# 08_INPUTCAPTURE_ENCODER.net
KiCad netlist of a schematic drawn in Altium Designer
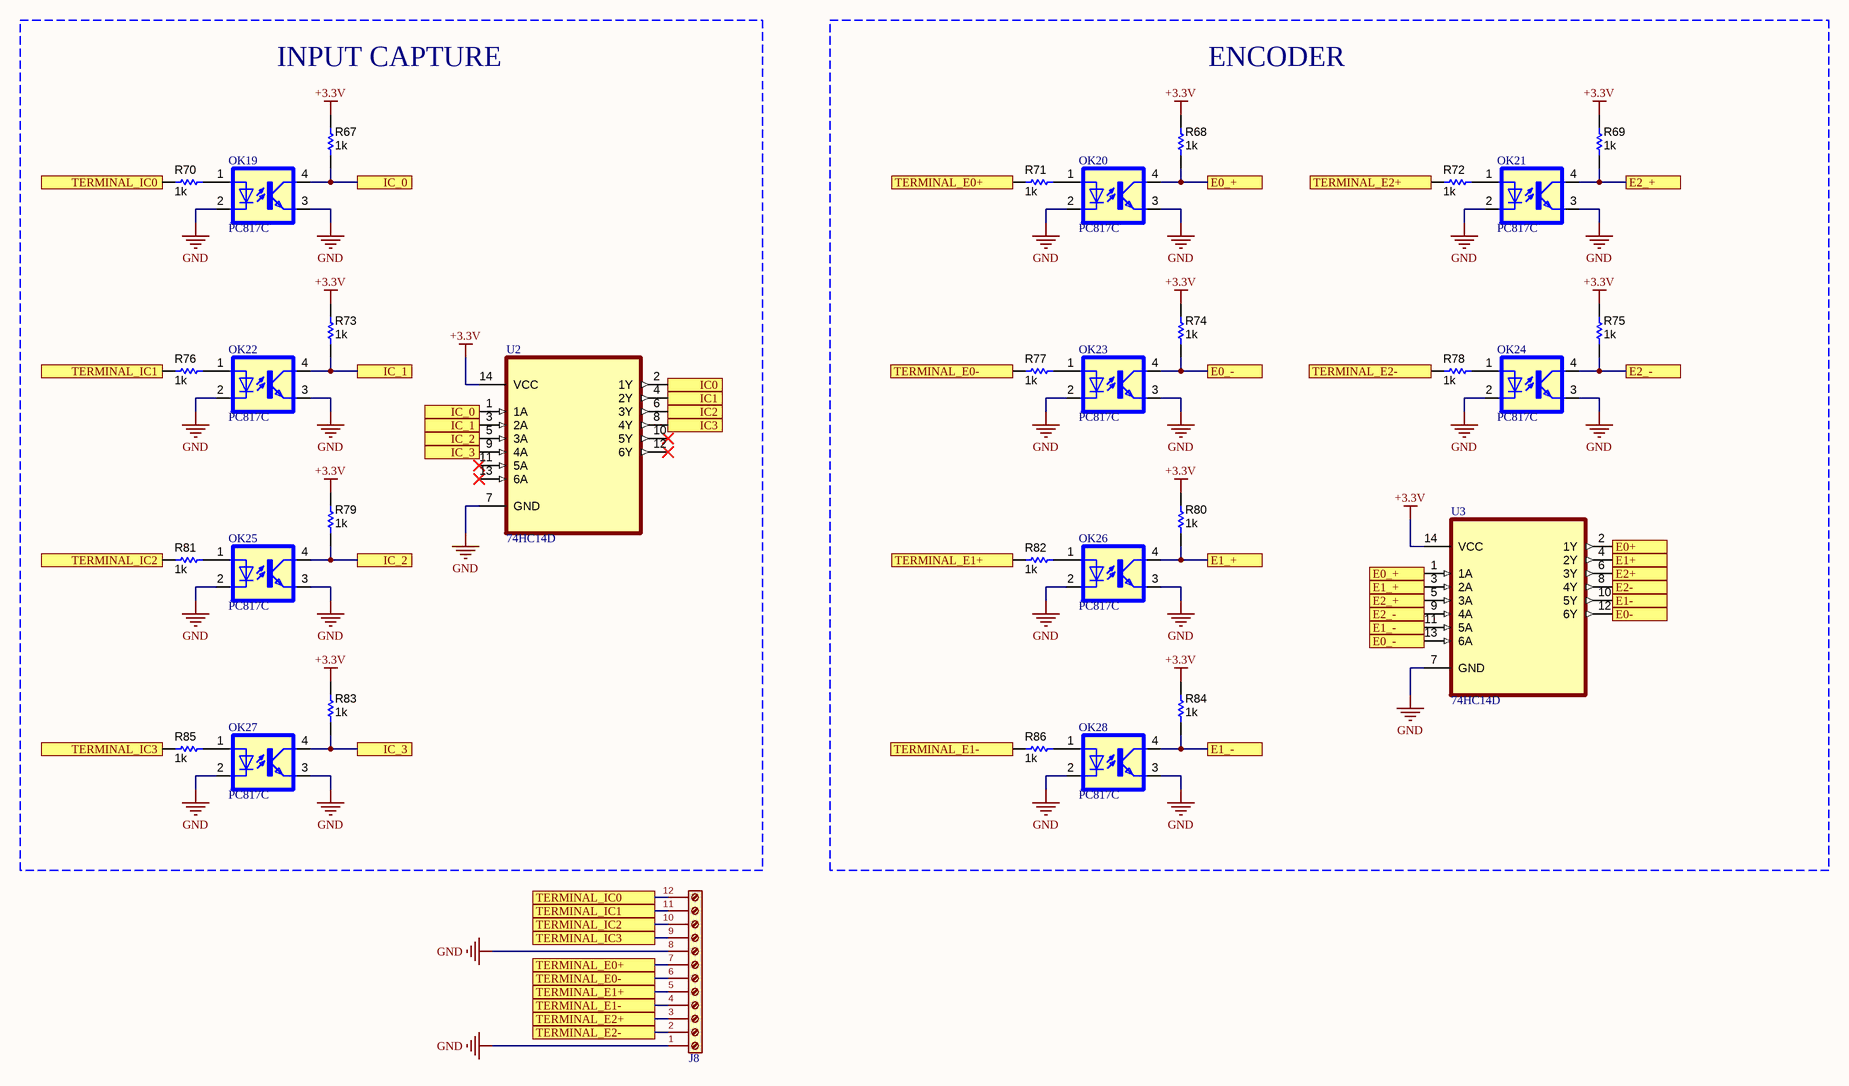
[diagram p0: 08_INPUTCAPTURE_ENCODER.SchDoc]

(export (version "E")
  (design (tool "Eeschema 10.0.6"))
  (components
    (comp (ref "J8")
      (value "Terminal_01x12_P5.00")
      (footprint "TerminalBlock_Phoenix_PT-1,5-12-5.0-H_1x12_P5.00mm_Horizontal")
      (libsource (lib "PROC051C_AWR1843BOOST_RevC") (part "Terminal_01x12_P5.00"))
    )
    (comp (ref "OK19")
      (value "PC817C")
      (footprint "SOP254P975X460-4N")
      (description "RF Mixer IC Cellular, DCS, PCS, W-CDMA, WLAN Up Converter 50MHz ~ 400MHz 6-SuperMiniMold")
      (fields (field (name "MF") "Renesas Electronics America Inc") (field (name "MP") "PC817"))
      (libsource (lib "PROC051C_AWR1843BOOST_RevC") (part "PC817C"))
    )
    (comp (ref "OK20")
      (value "PC817C")
      (footprint "SOP254P975X460-4N")
      (description "RF Mixer IC Cellular, DCS, PCS, W-CDMA, WLAN Up Converter 50MHz ~ 400MHz 6-SuperMiniMold")
      (fields (field (name "MF") "Renesas Electronics America Inc") (field (name "MP") "PC817"))
      (libsource (lib "PROC051C_AWR1843BOOST_RevC") (part "PC817C"))
    )
    (comp (ref "OK21")
      (value "PC817C")
      (footprint "SOP254P975X460-4N")
      (description "RF Mixer IC Cellular, DCS, PCS, W-CDMA, WLAN Up Converter 50MHz ~ 400MHz 6-SuperMiniMold")
      (fields (field (name "MF") "Renesas Electronics America Inc") (field (name "MP") "PC817"))
      (libsource (lib "PROC051C_AWR1843BOOST_RevC") (part "PC817C"))
    )
    (comp (ref "OK22")
      (value "PC817C")
      (footprint "SOP254P975X460-4N")
      (description "RF Mixer IC Cellular, DCS, PCS, W-CDMA, WLAN Up Converter 50MHz ~ 400MHz 6-SuperMiniMold")
      (fields (field (name "MF") "Renesas Electronics America Inc") (field (name "MP") "PC817"))
      (libsource (lib "PROC051C_AWR1843BOOST_RevC") (part "PC817C"))
    )
    (comp (ref "OK23")
      (value "PC817C")
      (footprint "SOP254P975X460-4N")
      (description "RF Mixer IC Cellular, DCS, PCS, W-CDMA, WLAN Up Converter 50MHz ~ 400MHz 6-SuperMiniMold")
      (fields (field (name "MF") "Renesas Electronics America Inc") (field (name "MP") "PC817"))
      (libsource (lib "PROC051C_AWR1843BOOST_RevC") (part "PC817C"))
    )
    (comp (ref "OK24")
      (value "PC817C")
      (footprint "SOP254P975X460-4N")
      (description "RF Mixer IC Cellular, DCS, PCS, W-CDMA, WLAN Up Converter 50MHz ~ 400MHz 6-SuperMiniMold")
      (fields (field (name "MF") "Renesas Electronics America Inc") (field (name "MP") "PC817"))
      (libsource (lib "PROC051C_AWR1843BOOST_RevC") (part "PC817C"))
    )
    (comp (ref "OK25")
      (value "PC817C")
      (footprint "SOP254P975X460-4N")
      (description "RF Mixer IC Cellular, DCS, PCS, W-CDMA, WLAN Up Converter 50MHz ~ 400MHz 6-SuperMiniMold")
      (fields (field (name "MF") "Renesas Electronics America Inc") (field (name "MP") "PC817"))
      (libsource (lib "PROC051C_AWR1843BOOST_RevC") (part "PC817C"))
    )
    (comp (ref "OK26")
      (value "PC817C")
      (footprint "SOP254P975X460-4N")
      (description "RF Mixer IC Cellular, DCS, PCS, W-CDMA, WLAN Up Converter 50MHz ~ 400MHz 6-SuperMiniMold")
      (fields (field (name "MF") "Renesas Electronics America Inc") (field (name "MP") "PC817"))
      (libsource (lib "PROC051C_AWR1843BOOST_RevC") (part "PC817C"))
    )
    (comp (ref "OK27")
      (value "PC817C")
      (footprint "SOP254P975X460-4N")
      (description "RF Mixer IC Cellular, DCS, PCS, W-CDMA, WLAN Up Converter 50MHz ~ 400MHz 6-SuperMiniMold")
      (fields (field (name "MF") "Renesas Electronics America Inc") (field (name "MP") "PC817"))
      (libsource (lib "PROC051C_AWR1843BOOST_RevC") (part "PC817C"))
    )
    (comp (ref "OK28")
      (value "PC817C")
      (footprint "SOP254P975X460-4N")
      (description "RF Mixer IC Cellular, DCS, PCS, W-CDMA, WLAN Up Converter 50MHz ~ 400MHz 6-SuperMiniMold")
      (fields (field (name "MF") "Renesas Electronics America Inc") (field (name "MP") "PC817"))
      (libsource (lib "PROC051C_AWR1843BOOST_RevC") (part "PC817C"))
    )
    (comp (ref "R67")
      (value "MCT06030Z0000ZP500")
      (footprint "0603")
      (description "RES, 0, 5%, 0.125 W, 0603")
      (fields
        (field (name "MANUFACTURER") "Vishay/Beyschlag")
        (field (name "VALUEDISPLAYED") "1k")
        (field (name "PUBLISHER") "Texas Instruments")
      )
      (libsource (lib "PROC051C_AWR1843BOOST_RevC") (part "RES 0R 0603"))
    )
    (comp (ref "R68")
      (value "MCT06030Z0000ZP500")
      (footprint "0603")
      (description "RES, 0, 5%, 0.125 W, 0603")
      (fields
        (field (name "MANUFACTURER") "Vishay/Beyschlag")
        (field (name "VALUEDISPLAYED") "1k")
        (field (name "PUBLISHER") "Texas Instruments")
      )
      (libsource (lib "PROC051C_AWR1843BOOST_RevC") (part "RES 0R 0603"))
    )
    (comp (ref "R69")
      (value "MCT06030Z0000ZP500")
      (footprint "0603")
      (description "RES, 0, 5%, 0.125 W, 0603")
      (fields
        (field (name "MANUFACTURER") "Vishay/Beyschlag")
        (field (name "VALUEDISPLAYED") "1k")
        (field (name "PUBLISHER") "Texas Instruments")
      )
      (libsource (lib "PROC051C_AWR1843BOOST_RevC") (part "RES 0R 0603"))
    )
    (comp (ref "R70")
      (value "MCT06030Z0000ZP500")
      (footprint "0603")
      (description "RES, 0, 5%, 0.125 W, 0603")
      (fields
        (field (name "MANUFACTURER") "Vishay/Beyschlag")
        (field (name "VALUEDISPLAYED") "1k")
        (field (name "PUBLISHER") "Texas Instruments")
      )
      (libsource (lib "PROC051C_AWR1843BOOST_RevC") (part "RES 0R 0603"))
    )
    (comp (ref "R71")
      (value "MCT06030Z0000ZP500")
      (footprint "0603")
      (description "RES, 0, 5%, 0.125 W, 0603")
      (fields
        (field (name "MANUFACTURER") "Vishay/Beyschlag")
        (field (name "VALUEDISPLAYED") "1k")
        (field (name "PUBLISHER") "Texas Instruments")
      )
      (libsource (lib "PROC051C_AWR1843BOOST_RevC") (part "RES 0R 0603"))
    )
    (comp (ref "R72")
      (value "MCT06030Z0000ZP500")
      (footprint "0603")
      (description "RES, 0, 5%, 0.125 W, 0603")
      (fields
        (field (name "MANUFACTURER") "Vishay/Beyschlag")
        (field (name "VALUEDISPLAYED") "1k")
        (field (name "PUBLISHER") "Texas Instruments")
      )
      (libsource (lib "PROC051C_AWR1843BOOST_RevC") (part "RES 0R 0603"))
    )
    (comp (ref "R73")
      (value "MCT06030Z0000ZP500")
      (footprint "0603")
      (description "RES, 0, 5%, 0.125 W, 0603")
      (fields
        (field (name "MANUFACTURER") "Vishay/Beyschlag")
        (field (name "VALUEDISPLAYED") "1k")
        (field (name "PUBLISHER") "Texas Instruments")
      )
      (libsource (lib "PROC051C_AWR1843BOOST_RevC") (part "RES 0R 0603"))
    )
    (comp (ref "R74")
      (value "MCT06030Z0000ZP500")
      (footprint "0603")
      (description "RES, 0, 5%, 0.125 W, 0603")
      (fields
        (field (name "MANUFACTURER") "Vishay/Beyschlag")
        (field (name "VALUEDISPLAYED") "1k")
        (field (name "PUBLISHER") "Texas Instruments")
      )
      (libsource (lib "PROC051C_AWR1843BOOST_RevC") (part "RES 0R 0603"))
    )
    (comp (ref "R75")
      (value "MCT06030Z0000ZP500")
      (footprint "0603")
      (description "RES, 0, 5%, 0.125 W, 0603")
      (fields
        (field (name "MANUFACTURER") "Vishay/Beyschlag")
        (field (name "VALUEDISPLAYED") "1k")
        (field (name "PUBLISHER") "Texas Instruments")
      )
      (libsource (lib "PROC051C_AWR1843BOOST_RevC") (part "RES 0R 0603"))
    )
    (comp (ref "R76")
      (value "MCT06030Z0000ZP500")
      (footprint "0603")
      (description "RES, 0, 5%, 0.125 W, 0603")
      (fields
        (field (name "MANUFACTURER") "Vishay/Beyschlag")
        (field (name "VALUEDISPLAYED") "1k")
        (field (name "PUBLISHER") "Texas Instruments")
      )
      (libsource (lib "PROC051C_AWR1843BOOST_RevC") (part "RES 0R 0603"))
    )
    (comp (ref "R77")
      (value "MCT06030Z0000ZP500")
      (footprint "0603")
      (description "RES, 0, 5%, 0.125 W, 0603")
      (fields
        (field (name "MANUFACTURER") "Vishay/Beyschlag")
        (field (name "VALUEDISPLAYED") "1k")
        (field (name "PUBLISHER") "Texas Instruments")
      )
      (libsource (lib "PROC051C_AWR1843BOOST_RevC") (part "RES 0R 0603"))
    )
    (comp (ref "R78")
      (value "MCT06030Z0000ZP500")
      (footprint "0603")
      (description "RES, 0, 5%, 0.125 W, 0603")
      (fields
        (field (name "MANUFACTURER") "Vishay/Beyschlag")
        (field (name "VALUEDISPLAYED") "1k")
        (field (name "PUBLISHER") "Texas Instruments")
      )
      (libsource (lib "PROC051C_AWR1843BOOST_RevC") (part "RES 0R 0603"))
    )
    (comp (ref "R79")
      (value "MCT06030Z0000ZP500")
      (footprint "0603")
      (description "RES, 0, 5%, 0.125 W, 0603")
      (fields
        (field (name "MANUFACTURER") "Vishay/Beyschlag")
        (field (name "VALUEDISPLAYED") "1k")
        (field (name "PUBLISHER") "Texas Instruments")
      )
      (libsource (lib "PROC051C_AWR1843BOOST_RevC") (part "RES 0R 0603"))
    )
    (comp (ref "R80")
      (value "MCT06030Z0000ZP500")
      (footprint "0603")
      (description "RES, 0, 5%, 0.125 W, 0603")
      (fields
        (field (name "MANUFACTURER") "Vishay/Beyschlag")
        (field (name "VALUEDISPLAYED") "1k")
        (field (name "PUBLISHER") "Texas Instruments")
      )
      (libsource (lib "PROC051C_AWR1843BOOST_RevC") (part "RES 0R 0603"))
    )
    (comp (ref "R81")
      (value "MCT06030Z0000ZP500")
      (footprint "0603")
      (description "RES, 0, 5%, 0.125 W, 0603")
      (fields
        (field (name "MANUFACTURER") "Vishay/Beyschlag")
        (field (name "VALUEDISPLAYED") "1k")
        (field (name "PUBLISHER") "Texas Instruments")
      )
      (libsource (lib "PROC051C_AWR1843BOOST_RevC") (part "RES 0R 0603"))
    )
    (comp (ref "R82")
      (value "MCT06030Z0000ZP500")
      (footprint "0603")
      (description "RES, 0, 5%, 0.125 W, 0603")
      (fields
        (field (name "MANUFACTURER") "Vishay/Beyschlag")
        (field (name "VALUEDISPLAYED") "1k")
        (field (name "PUBLISHER") "Texas Instruments")
      )
      (libsource (lib "PROC051C_AWR1843BOOST_RevC") (part "RES 0R 0603"))
    )
    (comp (ref "R83")
      (value "MCT06030Z0000ZP500")
      (footprint "0603")
      (description "RES, 0, 5%, 0.125 W, 0603")
      (fields
        (field (name "MANUFACTURER") "Vishay/Beyschlag")
        (field (name "VALUEDISPLAYED") "1k")
        (field (name "PUBLISHER") "Texas Instruments")
      )
      (libsource (lib "PROC051C_AWR1843BOOST_RevC") (part "RES 0R 0603"))
    )
    (comp (ref "R84")
      (value "MCT06030Z0000ZP500")
      (footprint "0603")
      (description "RES, 0, 5%, 0.125 W, 0603")
      (fields
        (field (name "MANUFACTURER") "Vishay/Beyschlag")
        (field (name "VALUEDISPLAYED") "1k")
        (field (name "PUBLISHER") "Texas Instruments")
      )
      (libsource (lib "PROC051C_AWR1843BOOST_RevC") (part "RES 0R 0603"))
    )
    (comp (ref "R85")
      (value "MCT06030Z0000ZP500")
      (footprint "0603")
      (description "RES, 0, 5%, 0.125 W, 0603")
      (fields
        (field (name "MANUFACTURER") "Vishay/Beyschlag")
        (field (name "VALUEDISPLAYED") "1k")
        (field (name "PUBLISHER") "Texas Instruments")
      )
      (libsource (lib "PROC051C_AWR1843BOOST_RevC") (part "RES 0R 0603"))
    )
    (comp (ref "R86")
      (value "MCT06030Z0000ZP500")
      (footprint "0603")
      (description "RES, 0, 5%, 0.125 W, 0603")
      (fields
        (field (name "MANUFACTURER") "Vishay/Beyschlag")
        (field (name "VALUEDISPLAYED") "1k")
        (field (name "PUBLISHER") "Texas Instruments")
      )
      (libsource (lib "PROC051C_AWR1843BOOST_RevC") (part "RES 0R 0603"))
    )
    (comp (ref "U2")
      (value "74HC14D")
      (footprint "SOIC127P600X175-14N")
      (description "Inverter IC 6 Channel Schmitt Trigger 14-SOIC")
      (fields (field (name "MF") "Toshiba"))
      (libsource (lib "PROC051C_AWR1843BOOST_RevC") (part "74HC14D"))
    )
    (comp (ref "U3")
      (value "74HC14D")
      (footprint "SOIC127P600X175-14N")
      (description "Inverter IC 6 Channel Schmitt Trigger 14-SOIC")
      (fields (field (name "MF") "Toshiba"))
      (libsource (lib "PROC051C_AWR1843BOOST_RevC") (part "74HC14D"))
    )
  )
  (nets
    (net (code "1") (name "+3.3V") (class "Default")
      (node (ref "R67") (pin "2") (pinfunction "2_2") (pintype "passive"))
      (node (ref "R68") (pin "2") (pinfunction "2_2") (pintype "passive"))
      (node (ref "R69") (pin "2") (pinfunction "2_2") (pintype "passive"))
      (node (ref "R73") (pin "2") (pinfunction "2_2") (pintype "passive"))
      (node (ref "R74") (pin "2") (pinfunction "2_2") (pintype "passive"))
      (node (ref "R75") (pin "2") (pinfunction "2_2") (pintype "passive"))
      (node (ref "R79") (pin "2") (pinfunction "2_2") (pintype "passive"))
      (node (ref "R80") (pin "2") (pinfunction "2_2") (pintype "passive"))
      (node (ref "R83") (pin "2") (pinfunction "2_2") (pintype "passive"))
      (node (ref "R84") (pin "2") (pinfunction "2_2") (pintype "passive"))
      (node (ref "U2") (pin "14") (pinfunction "VCC_14") (pintype "power_in"))
      (node (ref "U3") (pin "14") (pinfunction "VCC_14") (pintype "power_in"))
    )
    (net (code "2") (name "/E0+") (class "Default")
      (node (ref "U3") (pin "2") (pinfunction "1Y_2") (pintype "output"))
    )
    (net (code "3") (name "/E0-") (class "Default")
      (node (ref "U3") (pin "12") (pinfunction "6Y_12") (pintype "output"))
    )
    (net (code "4") (name "/E0_+") (class "Default")
      (node (ref "OK20") (pin "4") (pinfunction "COL_4") (pintype "passive"))
      (node (ref "R68") (pin "1") (pinfunction "1_1") (pintype "passive"))
      (node (ref "U3") (pin "1") (pinfunction "1A_1") (pintype "input"))
    )
    (net (code "5") (name "/E0_-") (class "Default")
      (node (ref "OK23") (pin "4") (pinfunction "COL_4") (pintype "passive"))
      (node (ref "R74") (pin "1") (pinfunction "1_1") (pintype "passive"))
      (node (ref "U3") (pin "13") (pinfunction "6A_13") (pintype "input"))
    )
    (net (code "6") (name "/E1+") (class "Default")
      (node (ref "U3") (pin "4") (pinfunction "2Y_4") (pintype "output"))
    )
    (net (code "7") (name "/E1-") (class "Default")
      (node (ref "U3") (pin "10") (pinfunction "5Y_10") (pintype "output"))
    )
    (net (code "8") (name "/E1_+") (class "Default")
      (node (ref "OK26") (pin "4") (pinfunction "COL_4") (pintype "passive"))
      (node (ref "R80") (pin "1") (pinfunction "1_1") (pintype "passive"))
      (node (ref "U3") (pin "3") (pinfunction "2A_3") (pintype "input"))
    )
    (net (code "9") (name "/E1_-") (class "Default")
      (node (ref "OK28") (pin "4") (pinfunction "COL_4") (pintype "passive"))
      (node (ref "R84") (pin "1") (pinfunction "1_1") (pintype "passive"))
      (node (ref "U3") (pin "11") (pinfunction "5A_11") (pintype "input"))
    )
    (net (code "10") (name "/E2+") (class "Default")
      (node (ref "U3") (pin "6") (pinfunction "3Y_6") (pintype "output"))
    )
    (net (code "11") (name "/E2-") (class "Default")
      (node (ref "U3") (pin "8") (pinfunction "4Y_8") (pintype "output"))
    )
    (net (code "12") (name "/E2_+") (class "Default")
      (node (ref "OK21") (pin "4") (pinfunction "COL_4") (pintype "passive"))
      (node (ref "R69") (pin "1") (pinfunction "1_1") (pintype "passive"))
      (node (ref "U3") (pin "5") (pinfunction "3A_5") (pintype "input"))
    )
    (net (code "13") (name "/E2_-") (class "Default")
      (node (ref "OK24") (pin "4") (pinfunction "COL_4") (pintype "passive"))
      (node (ref "R75") (pin "1") (pinfunction "1_1") (pintype "passive"))
      (node (ref "U3") (pin "9") (pinfunction "4A_9") (pintype "input"))
    )
    (net (code "14") (name "/IC0") (class "Default")
      (node (ref "U2") (pin "2") (pinfunction "1Y_2") (pintype "output"))
    )
    (net (code "15") (name "/IC1") (class "Default")
      (node (ref "U2") (pin "4") (pinfunction "2Y_4") (pintype "output"))
    )
    (net (code "16") (name "/IC2") (class "Default")
      (node (ref "U2") (pin "6") (pinfunction "3Y_6") (pintype "output"))
    )
    (net (code "17") (name "/IC3") (class "Default")
      (node (ref "U2") (pin "8") (pinfunction "4Y_8") (pintype "output"))
    )
    (net (code "18") (name "/IC_0") (class "Default")
      (node (ref "OK19") (pin "4") (pinfunction "COL_4") (pintype "passive"))
      (node (ref "R67") (pin "1") (pinfunction "1_1") (pintype "passive"))
      (node (ref "U2") (pin "1") (pinfunction "1A_1") (pintype "input"))
    )
    (net (code "19") (name "/IC_1") (class "Default")
      (node (ref "OK22") (pin "4") (pinfunction "COL_4") (pintype "passive"))
      (node (ref "R73") (pin "1") (pinfunction "1_1") (pintype "passive"))
      (node (ref "U2") (pin "3") (pinfunction "2A_3") (pintype "input"))
    )
    (net (code "20") (name "/IC_2") (class "Default")
      (node (ref "OK25") (pin "4") (pinfunction "COL_4") (pintype "passive"))
      (node (ref "R79") (pin "1") (pinfunction "1_1") (pintype "passive"))
      (node (ref "U2") (pin "5") (pinfunction "3A_5") (pintype "input"))
    )
    (net (code "21") (name "/IC_3") (class "Default")
      (node (ref "OK27") (pin "4") (pinfunction "COL_4") (pintype "passive"))
      (node (ref "R83") (pin "1") (pinfunction "1_1") (pintype "passive"))
      (node (ref "U2") (pin "9") (pinfunction "4A_9") (pintype "input"))
    )
    (net (code "22") (name "/TERMINAL_E0+") (class "Default")
      (node (ref "J8") (pin "7") (pinfunction "Pin_7_7") (pintype "passive"))
      (node (ref "R71") (pin "1") (pinfunction "1_1") (pintype "passive"))
    )
    (net (code "23") (name "/TERMINAL_E0-") (class "Default")
      (node (ref "J8") (pin "6") (pinfunction "Pin_6_6") (pintype "passive"))
      (node (ref "R77") (pin "1") (pinfunction "1_1") (pintype "passive"))
    )
    (net (code "24") (name "/TERMINAL_E1+") (class "Default")
      (node (ref "J8") (pin "5") (pinfunction "Pin_5_5") (pintype "passive"))
      (node (ref "R82") (pin "1") (pinfunction "1_1") (pintype "passive"))
    )
    (net (code "25") (name "/TERMINAL_E1-") (class "Default")
      (node (ref "J8") (pin "4") (pinfunction "Pin_4_4") (pintype "passive"))
      (node (ref "R86") (pin "1") (pinfunction "1_1") (pintype "passive"))
    )
    (net (code "26") (name "/TERMINAL_E2+") (class "Default")
      (node (ref "J8") (pin "3") (pinfunction "Pin_3_3") (pintype "passive"))
      (node (ref "R72") (pin "1") (pinfunction "1_1") (pintype "passive"))
    )
    (net (code "27") (name "/TERMINAL_E2-") (class "Default")
      (node (ref "J8") (pin "2") (pinfunction "Pin_2_2") (pintype "passive"))
      (node (ref "R78") (pin "1") (pinfunction "1_1") (pintype "passive"))
    )
    (net (code "28") (name "/TERMINAL_IC0") (class "Default")
      (node (ref "J8") (pin "12") (pinfunction "Pin_12_12") (pintype "passive"))
      (node (ref "R70") (pin "1") (pinfunction "1_1") (pintype "passive"))
    )
    (net (code "29") (name "/TERMINAL_IC1") (class "Default")
      (node (ref "J8") (pin "11") (pinfunction "Pin_11_11") (pintype "passive"))
      (node (ref "R76") (pin "1") (pinfunction "1_1") (pintype "passive"))
    )
    (net (code "30") (name "/TERMINAL_IC2") (class "Default")
      (node (ref "J8") (pin "10") (pinfunction "Pin_10_10") (pintype "passive"))
      (node (ref "R81") (pin "1") (pinfunction "1_1") (pintype "passive"))
    )
    (net (code "31") (name "/TERMINAL_IC3") (class "Default")
      (node (ref "J8") (pin "9") (pinfunction "Pin_9_9") (pintype "passive"))
      (node (ref "R85") (pin "1") (pinfunction "1_1") (pintype "passive"))
    )
    (net (code "32") (name "GND") (class "Default")
      (node (ref "J8") (pin "1") (pinfunction "Pin_1_1") (pintype "passive"))
      (node (ref "J8") (pin "8") (pinfunction "Pin_8_8") (pintype "passive"))
      (node (ref "OK19") (pin "2") (pinfunction "C_2") (pintype "passive"))
      (node (ref "OK19") (pin "3") (pinfunction "EMIT_3") (pintype "passive"))
      (node (ref "OK20") (pin "2") (pinfunction "C_2") (pintype "passive"))
      (node (ref "OK20") (pin "3") (pinfunction "EMIT_3") (pintype "passive"))
      (node (ref "OK21") (pin "2") (pinfunction "C_2") (pintype "passive"))
      (node (ref "OK21") (pin "3") (pinfunction "EMIT_3") (pintype "passive"))
      (node (ref "OK22") (pin "2") (pinfunction "C_2") (pintype "passive"))
      (node (ref "OK22") (pin "3") (pinfunction "EMIT_3") (pintype "passive"))
      (node (ref "OK23") (pin "2") (pinfunction "C_2") (pintype "passive"))
      (node (ref "OK23") (pin "3") (pinfunction "EMIT_3") (pintype "passive"))
      (node (ref "OK24") (pin "2") (pinfunction "C_2") (pintype "passive"))
      (node (ref "OK24") (pin "3") (pinfunction "EMIT_3") (pintype "passive"))
      (node (ref "OK25") (pin "2") (pinfunction "C_2") (pintype "passive"))
      (node (ref "OK25") (pin "3") (pinfunction "EMIT_3") (pintype "passive"))
      (node (ref "OK26") (pin "2") (pinfunction "C_2") (pintype "passive"))
      (node (ref "OK26") (pin "3") (pinfunction "EMIT_3") (pintype "passive"))
      (node (ref "OK27") (pin "2") (pinfunction "C_2") (pintype "passive"))
      (node (ref "OK27") (pin "3") (pinfunction "EMIT_3") (pintype "passive"))
      (node (ref "OK28") (pin "2") (pinfunction "C_2") (pintype "passive"))
      (node (ref "OK28") (pin "3") (pinfunction "EMIT_3") (pintype "passive"))
      (node (ref "U2") (pin "7") (pinfunction "GND_7") (pintype "passive"))
      (node (ref "U3") (pin "7") (pinfunction "GND_7") (pintype "passive"))
    )
    (net (code "33") (name "Net-(OK19-A)") (class "Default")
      (node (ref "OK19") (pin "1") (pinfunction "A_1") (pintype "passive"))
      (node (ref "R70") (pin "2") (pinfunction "2_2") (pintype "passive"))
    )
    (net (code "34") (name "Net-(OK20-A)") (class "Default")
      (node (ref "OK20") (pin "1") (pinfunction "A_1") (pintype "passive"))
      (node (ref "R71") (pin "2") (pinfunction "2_2") (pintype "passive"))
    )
    (net (code "35") (name "Net-(OK21-A)") (class "Default")
      (node (ref "OK21") (pin "1") (pinfunction "A_1") (pintype "passive"))
      (node (ref "R72") (pin "2") (pinfunction "2_2") (pintype "passive"))
    )
    (net (code "36") (name "Net-(OK22-A)") (class "Default")
      (node (ref "OK22") (pin "1") (pinfunction "A_1") (pintype "passive"))
      (node (ref "R76") (pin "2") (pinfunction "2_2") (pintype "passive"))
    )
    (net (code "37") (name "Net-(OK23-A)") (class "Default")
      (node (ref "OK23") (pin "1") (pinfunction "A_1") (pintype "passive"))
      (node (ref "R77") (pin "2") (pinfunction "2_2") (pintype "passive"))
    )
    (net (code "38") (name "Net-(OK24-A)") (class "Default")
      (node (ref "OK24") (pin "1") (pinfunction "A_1") (pintype "passive"))
      (node (ref "R78") (pin "2") (pinfunction "2_2") (pintype "passive"))
    )
    (net (code "39") (name "Net-(OK25-A)") (class "Default")
      (node (ref "OK25") (pin "1") (pinfunction "A_1") (pintype "passive"))
      (node (ref "R81") (pin "2") (pinfunction "2_2") (pintype "passive"))
    )
    (net (code "40") (name "Net-(OK26-A)") (class "Default")
      (node (ref "OK26") (pin "1") (pinfunction "A_1") (pintype "passive"))
      (node (ref "R82") (pin "2") (pinfunction "2_2") (pintype "passive"))
    )
    (net (code "41") (name "Net-(OK27-A)") (class "Default")
      (node (ref "OK27") (pin "1") (pinfunction "A_1") (pintype "passive"))
      (node (ref "R85") (pin "2") (pinfunction "2_2") (pintype "passive"))
    )
    (net (code "42") (name "Net-(OK28-A)") (class "Default")
      (node (ref "OK28") (pin "1") (pinfunction "A_1") (pintype "passive"))
      (node (ref "R86") (pin "2") (pinfunction "2_2") (pintype "passive"))
    )
    (net (code "43") (name "unconnected-(U2-5A-Pad11)") (class "Default")
      (node (ref "U2") (pin "11") (pinfunction "5A_11") (pintype "input+no_connect"))
    )
    (net (code "44") (name "unconnected-(U2-5Y-Pad10)") (class "Default")
      (node (ref "U2") (pin "10") (pinfunction "5Y_10") (pintype "output+no_connect"))
    )
    (net (code "45") (name "unconnected-(U2-6A-Pad13)") (class "Default")
      (node (ref "U2") (pin "13") (pinfunction "6A_13") (pintype "input+no_connect"))
    )
    (net (code "46") (name "unconnected-(U2-6Y-Pad12)") (class "Default")
      (node (ref "U2") (pin "12") (pinfunction "6Y_12") (pintype "output+no_connect"))
    )
  )
)
